# Ruby.net
KiCad netlist of a schematic drawn in EAGLE
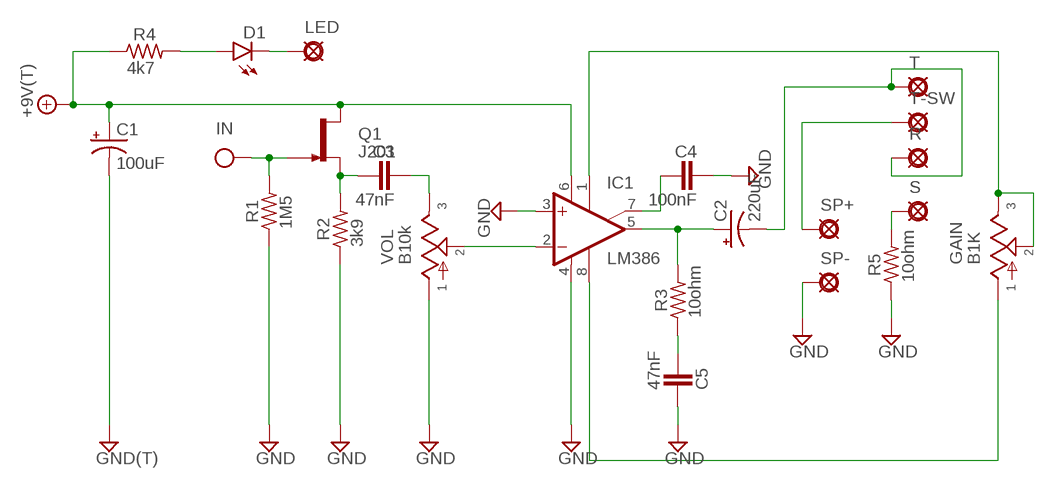
[diagram p0: schematic, sheet 1]

(export (version "E")
  (design (tool "Eeschema 10.0.6"))
  (components
    (comp (ref "+9V")
      (value "+9V(T)")
      (footprint "eagle-import:SQUARE")
      (libsource (lib "eagle-import") (part "+9V(T)"))
    )
    (comp (ref "C1")
      (value "100uF")
      (footprint "eagle-import:063_025")
      (libsource (lib "eagle-import") (part "0631"))
    )
    (comp (ref "C2")
      (value "220uF")
      (footprint "eagle-import:080_035_1")
      (libsource (lib "eagle-import") (part "0801"))
    )
    (comp (ref "C3")
      (value "47nF")
      (footprint "eagle-import:072X035")
      (libsource (lib "eagle-import") (part "072X0352"))
    )
    (comp (ref "C4")
      (value "100nF")
      (footprint "eagle-import:072X035")
      (libsource (lib "eagle-import") (part "072X0352"))
    )
    (comp (ref "C5")
      (value "47nF")
      (footprint "eagle-import:072X035")
      (libsource (lib "eagle-import") (part "072X0352"))
    )
    (comp (ref "D1")
      (value "LED3MM")
      (footprint "eagle-import:LED3MM")
      (libsource (lib "eagle-import") (part "LED3MM"))
    )
    (comp (ref "GAIN")
      (value "B1K")
      (footprint "eagle-import:16MM")
      (libsource (lib "eagle-import") (part "POT16MM"))
    )
    (comp (ref "GND")
      (value "GND(T)")
      (footprint "eagle-import:SQUARE")
      (libsource (lib "eagle-import") (part "GND(T)"))
    )
    (comp (ref "IC1")
      (value "LM386")
      (footprint "eagle-import:DIL08")
      (libsource (lib "eagle-import") (part "LM386"))
    )
    (comp (ref "IN")
      (value "IN(T)")
      (footprint "eagle-import:SQUARE")
      (libsource (lib "eagle-import") (part "IN(T)"))
    )
    (comp (ref "LED")
      (value "PAD")
      (footprint "eagle-import:SQUARE")
      (libsource (lib "eagle-import") (part "PAD"))
    )
    (comp (ref "Q1")
      (value "J201")
      (footprint "eagle-import:TO92-")
      (libsource (lib "eagle-import") (part "J201"))
    )
    (comp (ref "R")
      (value "PAD")
      (footprint "eagle-import:SQUARE")
      (libsource (lib "eagle-import") (part "PAD"))
    )
    (comp (ref "R1")
      (value "1M5")
      (footprint "eagle-import:R0207_3")
      (libsource (lib "eagle-import") (part "6MM.3"))
    )
    (comp (ref "R2")
      (value "3k9")
      (footprint "eagle-import:R0207_3")
      (libsource (lib "eagle-import") (part "6MM.3"))
    )
    (comp (ref "R3")
      (value "10ohm")
      (footprint "eagle-import:R0207_3")
      (libsource (lib "eagle-import") (part "6MM.3"))
    )
    (comp (ref "R4")
      (value "4k7")
      (footprint "eagle-import:R0207_3")
      (libsource (lib "eagle-import") (part "6MM.3"))
    )
    (comp (ref "R5")
      (value "10ohm")
      (footprint "eagle-import:R0207_3")
      (libsource (lib "eagle-import") (part "6MM.3"))
    )
    (comp (ref "S")
      (value "PADO")
      (footprint "eagle-import:ROUND")
      (libsource (lib "eagle-import") (part "PADO"))
    )
    (comp (ref "SP+")
      (value "PAD")
      (footprint "eagle-import:SQUARE")
      (libsource (lib "eagle-import") (part "PAD"))
    )
    (comp (ref "SP-")
      (value "PADO")
      (footprint "eagle-import:ROUND")
      (libsource (lib "eagle-import") (part "PADO"))
    )
    (comp (ref "T")
      (value "PAD")
      (footprint "eagle-import:SQUARE")
      (libsource (lib "eagle-import") (part "PAD"))
    )
    (comp (ref "T-SW")
      (value "PAD")
      (footprint "eagle-import:SQUARE")
      (libsource (lib "eagle-import") (part "PAD"))
    )
    (comp (ref "VOL")
      (value "B10k")
      (footprint "eagle-import:16MM")
      (libsource (lib "eagle-import") (part "POT16MM"))
    )
  )
  (nets
    (net (code "1") (name "+9V(T)") (class "Default")
      (node (ref "+9V") (pin "1") (pinfunction "+9V_1") (pintype "power_in"))
      (node (ref "C1") (pin "+") (pinfunction "+_+") (pintype "passive"))
      (node (ref "IC1") (pin "6") (pinfunction "V+_6") (pintype "power_in"))
      (node (ref "Q1") (pin "3") (pinfunction "D_3") (pintype "passive"))
      (node (ref "R4") (pin "1") (pinfunction "1_1") (pintype "passive"))
    )
    (net (code "2") (name "GND") (class "Default")
      (node (ref "C1") (pin "-") (pinfunction "-_-") (pintype "passive"))
      (node (ref "C4") (pin "2") (pinfunction "2_2") (pintype "passive"))
      (node (ref "C5") (pin "2") (pinfunction "2_2") (pintype "passive"))
      (node (ref "GND") (pin "1") (pinfunction "GND_1") (pintype "power_in"))
      (node (ref "IC1") (pin "3") (pinfunction "+IN_3") (pintype "input"))
      (node (ref "IC1") (pin "4") (pinfunction "V-_4") (pintype "power_in"))
      (node (ref "R1") (pin "1") (pinfunction "1_1") (pintype "passive"))
      (node (ref "R2") (pin "1") (pinfunction "1_1") (pintype "passive"))
      (node (ref "R5") (pin "1") (pinfunction "1_1") (pintype "passive"))
      (node (ref "SP-") (pin "1") (pinfunction "PAD_1") (pintype "passive"))
      (node (ref "VOL") (pin "1") (pinfunction "1_1") (pintype "passive"))
    )
    (net (code "3") (name "IN(T)") (class "Default")
      (node (ref "IN") (pin "1") (pinfunction "IN_1") (pintype "power_in"))
      (node (ref "Q1") (pin "1") (pinfunction "G_1") (pintype "passive"))
      (node (ref "R1") (pin "2") (pinfunction "2_2") (pintype "passive"))
    )
    (net (code "4") (name "Net-(C3-Pad2)") (class "Default")
      (node (ref "C3") (pin "2") (pinfunction "2_2") (pintype "passive"))
      (node (ref "VOL") (pin "3") (pinfunction "3_3") (pintype "passive"))
    )
    (net (code "5") (name "Net-(C5-Pad1)") (class "Default")
      (node (ref "C5") (pin "1") (pinfunction "1_1") (pintype "passive"))
      (node (ref "R3") (pin "1") (pinfunction "1_1") (pintype "passive"))
    )
    (net (code "6") (name "Net-(D1-C)") (class "Default")
      (node (ref "D1") (pin "K") (pinfunction "C_K") (pintype "passive"))
      (node (ref "LED") (pin "1") (pinfunction "PAD_1") (pintype "passive"))
    )
    (net (code "7") (name "Net-(D1-PadA)") (class "Default")
      (node (ref "D1") (pin "A") (pinfunction "A_A") (pintype "passive"))
      (node (ref "R4") (pin "2") (pinfunction "2_2") (pintype "passive"))
    )
    (net (code "8") (name "Net-(IC1--IN)") (class "Default")
      (node (ref "IC1") (pin "2") (pinfunction "-IN_2") (pintype "input"))
      (node (ref "VOL") (pin "2") (pinfunction "2_2") (pintype "passive"))
    )
    (net (code "9") (name "Net-(IC1-BYPASS)") (class "Default")
      (node (ref "C4") (pin "1") (pinfunction "1_1") (pintype "passive"))
      (node (ref "IC1") (pin "7") (pinfunction "BYPASS_7") (pintype "passive"))
    )
    (net (code "10") (name "Net-(IC1-GAIN1)") (class "Default")
      (node (ref "GAIN") (pin "2") (pinfunction "2_2") (pintype "passive"))
      (node (ref "GAIN") (pin "3") (pinfunction "3_3") (pintype "passive"))
      (node (ref "IC1") (pin "1") (pinfunction "GAIN1_1") (pintype "passive"))
    )
    (net (code "11") (name "Net-(IC1-GAIN2)") (class "Default")
      (node (ref "GAIN") (pin "1") (pinfunction "1_1") (pintype "passive"))
      (node (ref "IC1") (pin "8") (pinfunction "GAIN2_8") (pintype "passive"))
    )
    (net (code "12") (name "Net-(IC1-OUT)") (class "Default")
      (node (ref "C2") (pin "+") (pinfunction "+_+") (pintype "passive"))
      (node (ref "IC1") (pin "5") (pinfunction "OUT_5") (pintype "output"))
      (node (ref "R3") (pin "2") (pinfunction "2_2") (pintype "passive"))
    )
    (net (code "13") (name "Net-(Q1-S)") (class "Default")
      (node (ref "C3") (pin "1") (pinfunction "1_1") (pintype "passive"))
      (node (ref "Q1") (pin "2") (pinfunction "S_2") (pintype "passive"))
      (node (ref "R2") (pin "2") (pinfunction "2_2") (pintype "passive"))
    )
    (net (code "14") (name "Net-(R-PAD)") (class "Default")
      (node (ref "C2") (pin "-") (pinfunction "-_-") (pintype "passive"))
      (node (ref "R") (pin "1") (pinfunction "PAD_1") (pintype "passive"))
      (node (ref "T") (pin "1") (pinfunction "PAD_1") (pintype "passive"))
    )
    (net (code "15") (name "Net-(S-PAD)") (class "Default")
      (node (ref "R5") (pin "2") (pinfunction "2_2") (pintype "passive"))
      (node (ref "S") (pin "1") (pinfunction "PAD_1") (pintype "passive"))
    )
    (net (code "16") (name "Net-(SP+-PAD)") (class "Default")
      (node (ref "SP+") (pin "1") (pinfunction "PAD_1") (pintype "passive"))
      (node (ref "T-SW") (pin "1") (pinfunction "PAD_1") (pintype "passive"))
    )
  )
)
